# A702X.net
KiCad netlist of a schematic drawn in EAGLE
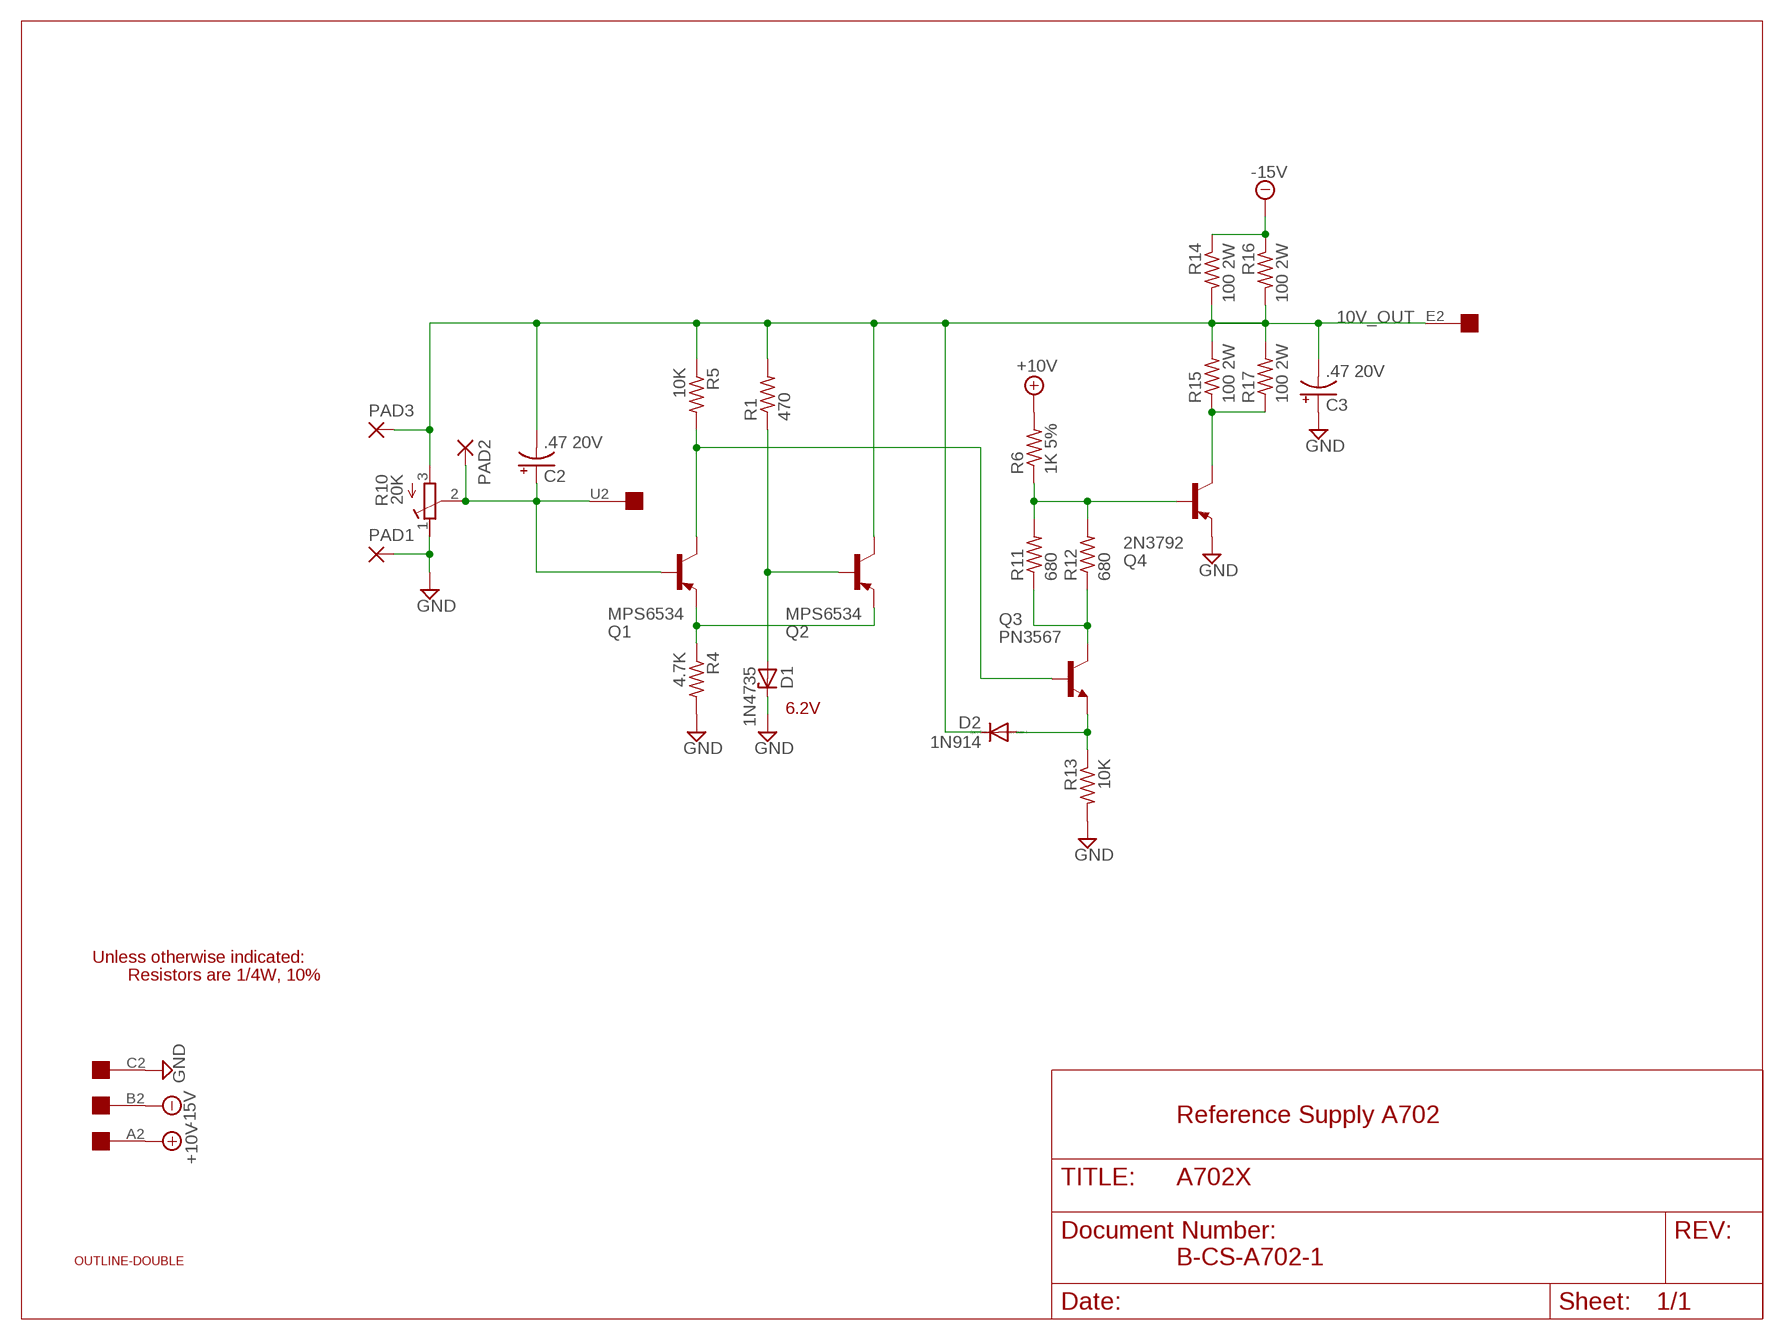
[diagram p0: schematic, sheet 1]

(export (version "E")
  (design (tool "Eeschema 10.0.6"))
  (components
    (comp (ref "C2")
      (value ".47 20V")
      (footprint "eagle-import:E22-6")
      (libsource (lib "eagle-import") (part "CPOL-USE22-6AXIAL"))
    )
    (comp (ref "C3")
      (value ".47 20V")
      (footprint "eagle-import:E22-6")
      (libsource (lib "eagle-import") (part "CPOL-USE22-6AXIAL"))
    )
    (comp (ref "D1")
      (value "1N4735")
      (footprint "eagle-import:DO35Z10")
      (libsource (lib "eagle-import") (part "1N821"))
    )
    (comp (ref "D2")
      (value "1N914")
      (footprint "eagle-import:DO35-10")
      (libsource (lib "eagle-import") (part "1N4148DO35-10"))
    )
    (comp (ref "PAD1")
      (value "2,54/0,8")
      (footprint "eagle-import:2,54_0,8")
      (libsource (lib "eagle-import") (part "2,54/0,8"))
    )
    (comp (ref "PAD2")
      (value "2,54/0,8")
      (footprint "eagle-import:2,54_0,8")
      (libsource (lib "eagle-import") (part "2,54/0,8"))
    )
    (comp (ref "PAD3")
      (value "2,54/0,8")
      (footprint "eagle-import:2,54_0,8")
      (libsource (lib "eagle-import") (part "2,54/0,8"))
    )
    (comp (ref "Q1")
      (value "MPS6534")
      (footprint "eagle-import:TO39")
      (libsource (lib "eagle-import") (part "2N2904A"))
    )
    (comp (ref "Q2")
      (value "MPS6534")
      (footprint "eagle-import:TO39")
      (libsource (lib "eagle-import") (part "2N2904A"))
    )
    (comp (ref "Q3")
      (value "PN3567")
      (footprint "eagle-import:TO5")
      (libsource (lib "eagle-import") (part "2N2219"))
    )
    (comp (ref "Q4")
      (value "2N3792")
      (footprint "eagle-import:TO3")
      (libsource (lib "eagle-import") (part "-PNP-TO3"))
    )
    (comp (ref "R1")
      (value "470")
      (footprint "eagle-import:0207_10")
      (libsource (lib "eagle-import") (part "R-US_0207/10"))
    )
    (comp (ref "R4")
      (value "4.7K")
      (footprint "eagle-import:0207_10")
      (libsource (lib "eagle-import") (part "R-US_0207/10"))
    )
    (comp (ref "R5")
      (value "10K")
      (footprint "eagle-import:0207_10")
      (libsource (lib "eagle-import") (part "R-US_0207/10"))
    )
    (comp (ref "R6")
      (value "1K 5%")
      (footprint "eagle-import:0207_10")
      (libsource (lib "eagle-import") (part "R-US_0207/10"))
    )
    (comp (ref "R10")
      (value "20K")
      (footprint "eagle-import:3006Y")
      (libsource (lib "eagle-import") (part "275P"))
    )
    (comp (ref "R11")
      (value "680")
      (footprint "eagle-import:0207_10")
      (libsource (lib "eagle-import") (part "R-US_0207/10"))
    )
    (comp (ref "R12")
      (value "680")
      (footprint "eagle-import:0207_10")
      (libsource (lib "eagle-import") (part "R-US_0207/10"))
    )
    (comp (ref "R13")
      (value "10K")
      (footprint "eagle-import:0207_10")
      (libsource (lib "eagle-import") (part "R-US_0207/10"))
    )
    (comp (ref "R14")
      (value "100 2W")
      (footprint "eagle-import:P0817_22")
      (libsource (lib "eagle-import") (part "R-US_0817/22"))
    )
    (comp (ref "R15")
      (value "100 2W")
      (footprint "eagle-import:P0817_22")
      (libsource (lib "eagle-import") (part "R-US_0817/22"))
    )
    (comp (ref "R16")
      (value "100 2W")
      (footprint "eagle-import:P0817_22")
      (libsource (lib "eagle-import") (part "R-US_0817/22"))
    )
    (comp (ref "R17")
      (value "100 2W")
      (footprint "eagle-import:P0817_22")
      (libsource (lib "eagle-import") (part "R-US_0817/22"))
    )
    (comp (ref "U$1")
      (value "OUTLINE-DOUBLE")
      (footprint "eagle-import:DOUBLE")
      (libsource (lib "eagle-import") (part "OUTLINE-DOUBLE"))
    )
    (comp (ref "U$3")
      (value "EDGE-1")
      (footprint "eagle-import:EDGE-CON1")
      (libsource (lib "eagle-import") (part "EDGE-1"))
    )
  )
  (nets
    (net (code "1") (name "+10V") (class "Default")
      (node (ref "R6") (pin "2") (pinfunction "2_2") (pintype "passive"))
      (node (ref "U$3") (pin "A2") (pinfunction "1_A2") (pintype "bidirectional"))
    )
    (net (code "2") (name "-15V") (class "Default")
      (node (ref "R14") (pin "1") (pinfunction "1_1") (pintype "passive"))
      (node (ref "R16") (pin "1") (pinfunction "1_1") (pintype "passive"))
      (node (ref "U$3") (pin "B2") (pinfunction "1_B2") (pintype "bidirectional"))
    )
    (net (code "3") (name "/10V_OUT") (class "Default")
      (node (ref "C2") (pin "-") (pinfunction "-_-") (pintype "passive"))
      (node (ref "C3") (pin "-") (pinfunction "-_-") (pintype "passive"))
      (node (ref "D2") (pin "C") (pinfunction "C_C") (pintype "passive"))
      (node (ref "PAD3") (pin "1") (pinfunction "P_1") (pintype "passive"))
      (node (ref "Q2") (pin "3") (pinfunction "C_3") (pintype "passive"))
      (node (ref "R1") (pin "2") (pinfunction "2_2") (pintype "passive"))
      (node (ref "R10") (pin "3") (pinfunction "E_3") (pintype "passive"))
      (node (ref "R14") (pin "2") (pinfunction "2_2") (pintype "passive"))
      (node (ref "R15") (pin "2") (pinfunction "2_2") (pintype "passive"))
      (node (ref "R16") (pin "2") (pinfunction "2_2") (pintype "passive"))
      (node (ref "R17") (pin "2") (pinfunction "2_2") (pintype "passive"))
      (node (ref "R5") (pin "1") (pinfunction "1_1") (pintype "passive"))
      (node (ref "U$3") (pin "E2") (pinfunction "1_E2") (pintype "bidirectional"))
    )
    (net (code "4") (name "GND") (class "Default")
      (node (ref "C3") (pin "+") (pinfunction "+_+") (pintype "passive"))
      (node (ref "D1") (pin "C") (pinfunction "C_C") (pintype "passive"))
      (node (ref "PAD1") (pin "1") (pinfunction "P_1") (pintype "passive"))
      (node (ref "Q4") (pin "E") (pinfunction "E_E") (pintype "passive"))
      (node (ref "R10") (pin "1") (pinfunction "A_1") (pintype "passive"))
      (node (ref "R13") (pin "2") (pinfunction "2_2") (pintype "passive"))
      (node (ref "R4") (pin "2") (pinfunction "2_2") (pintype "passive"))
      (node (ref "U$3") (pin "C2") (pinfunction "1_C2") (pintype "bidirectional"))
    )
    (net (code "5") (name "Net-(PAD2-P)") (class "Default")
      (node (ref "C2") (pin "+") (pinfunction "+_+") (pintype "passive"))
      (node (ref "PAD2") (pin "1") (pinfunction "P_1") (pintype "passive"))
      (node (ref "Q1") (pin "2") (pinfunction "B_2") (pintype "passive"))
      (node (ref "R10") (pin "2") (pinfunction "S_2") (pintype "passive"))
      (node (ref "U$3") (pin "U2") (pinfunction "1_U2") (pintype "bidirectional"))
    )
    (net (code "6") (name "Net-(Q1-C)") (class "Default")
      (node (ref "Q1") (pin "3") (pinfunction "C_3") (pintype "passive"))
      (node (ref "Q3") (pin "2") (pinfunction "B_2") (pintype "passive"))
      (node (ref "R5") (pin "2") (pinfunction "2_2") (pintype "passive"))
    )
    (net (code "7") (name "Net-(Q1-E)") (class "Default")
      (node (ref "Q1") (pin "1") (pinfunction "E_1") (pintype "passive"))
      (node (ref "Q2") (pin "1") (pinfunction "E_1") (pintype "passive"))
      (node (ref "R4") (pin "1") (pinfunction "1_1") (pintype "passive"))
    )
    (net (code "8") (name "Net-(Q2-B)") (class "Default")
      (node (ref "D1") (pin "A") (pinfunction "A_A") (pintype "passive"))
      (node (ref "Q2") (pin "2") (pinfunction "B_2") (pintype "passive"))
      (node (ref "R1") (pin "1") (pinfunction "1_1") (pintype "passive"))
    )
    (net (code "9") (name "Net-(Q3-C)") (class "Default")
      (node (ref "Q3") (pin "3") (pinfunction "C_3") (pintype "passive"))
      (node (ref "R11") (pin "1") (pinfunction "1_1") (pintype "passive"))
      (node (ref "R12") (pin "1") (pinfunction "1_1") (pintype "passive"))
    )
    (net (code "10") (name "Net-(Q3-E)") (class "Default")
      (node (ref "D2") (pin "A") (pinfunction "A_A") (pintype "passive"))
      (node (ref "Q3") (pin "1") (pinfunction "E_1") (pintype "passive"))
      (node (ref "R13") (pin "1") (pinfunction "1_1") (pintype "passive"))
    )
    (net (code "11") (name "Net-(Q4-PadB)") (class "Default")
      (node (ref "Q4") (pin "B") (pinfunction "B_B") (pintype "passive"))
      (node (ref "R11") (pin "2") (pinfunction "2_2") (pintype "passive"))
      (node (ref "R12") (pin "2") (pinfunction "2_2") (pintype "passive"))
      (node (ref "R6") (pin "1") (pinfunction "1_1") (pintype "passive"))
    )
    (net (code "12") (name "Net-(Q4-PadC)") (class "Default")
      (node (ref "Q4") (pin "C") (pinfunction "C_C") (pintype "passive"))
      (node (ref "R15") (pin "1") (pinfunction "1_1") (pintype "passive"))
      (node (ref "R17") (pin "1") (pinfunction "1_1") (pintype "passive"))
    )
  )
)
